# 5V_LD1117DT50CTR.net
KiCad netlist of a schematic drawn in Altium Designer
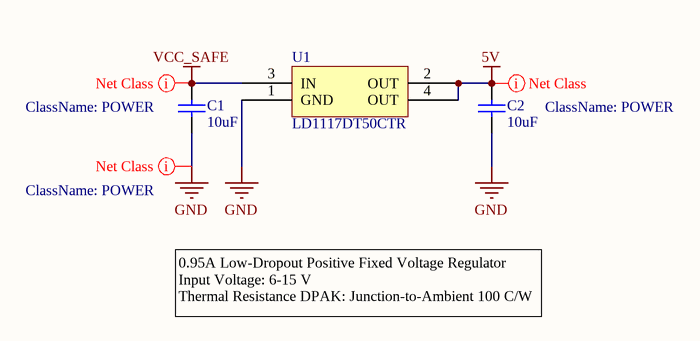
[diagram p0: 5V LD1117DT50CTR.SchDoc]

(export (version "E")
  (design (tool "Eeschema 10.0.6"))
  (components
    (comp (ref "C1")
      (value "10uF")
      (footprint "agh_racing_2018:CAP_0603_IPC_MD")
      (description "Capacitor")
      (fields (field (name "Comment") "Cap"))
      (libsource (lib "agh_racing_2018") (part "Cap"))
    )
    (comp (ref "C2")
      (value "10uF")
      (footprint "agh_racing_2018:CAP_0603_IPC_MD")
      (description "Capacitor")
      (fields (field (name "Comment") "Cap"))
      (libsource (lib "agh_racing_2018") (part "Cap"))
    )
    (comp (ref "U1")
      (value "LD1117DT50CTR")
      (footprint "DPAK_IPC_MD")
      (fields (field (name "MANUFACTURER") "ST Microelectronics"))
      (libsource (lib "agh_racing_2018") (part "LDO"))
    )
  )
  (nets
    (net (code "1") (name "5V") (class "Default")
      (node (ref "C2") (pin "2") (pinfunction "2_2") (pintype "passive"))
      (node (ref "U1") (pin "2") (pinfunction "OUT_2") (pintype "power_in"))
      (node (ref "U1") (pin "4") (pinfunction "OUT_4") (pintype "power_in"))
    )
    (net (code "2") (name "GND") (class "Default")
      (node (ref "C1") (pin "1") (pinfunction "1_1") (pintype "passive"))
      (node (ref "C2") (pin "1") (pinfunction "1_1") (pintype "passive"))
      (node (ref "U1") (pin "1") (pinfunction "GND_1") (pintype "power_in"))
    )
    (net (code "3") (name "VCC_SAFE") (class "Default")
      (node (ref "C1") (pin "2") (pinfunction "2_2") (pintype "passive"))
      (node (ref "U1") (pin "3") (pinfunction "IN_3") (pintype "power_in"))
    )
  )
)
